# SCH_smartFemX.net
KiCad netlist of a schematic drawn in EasyEDA
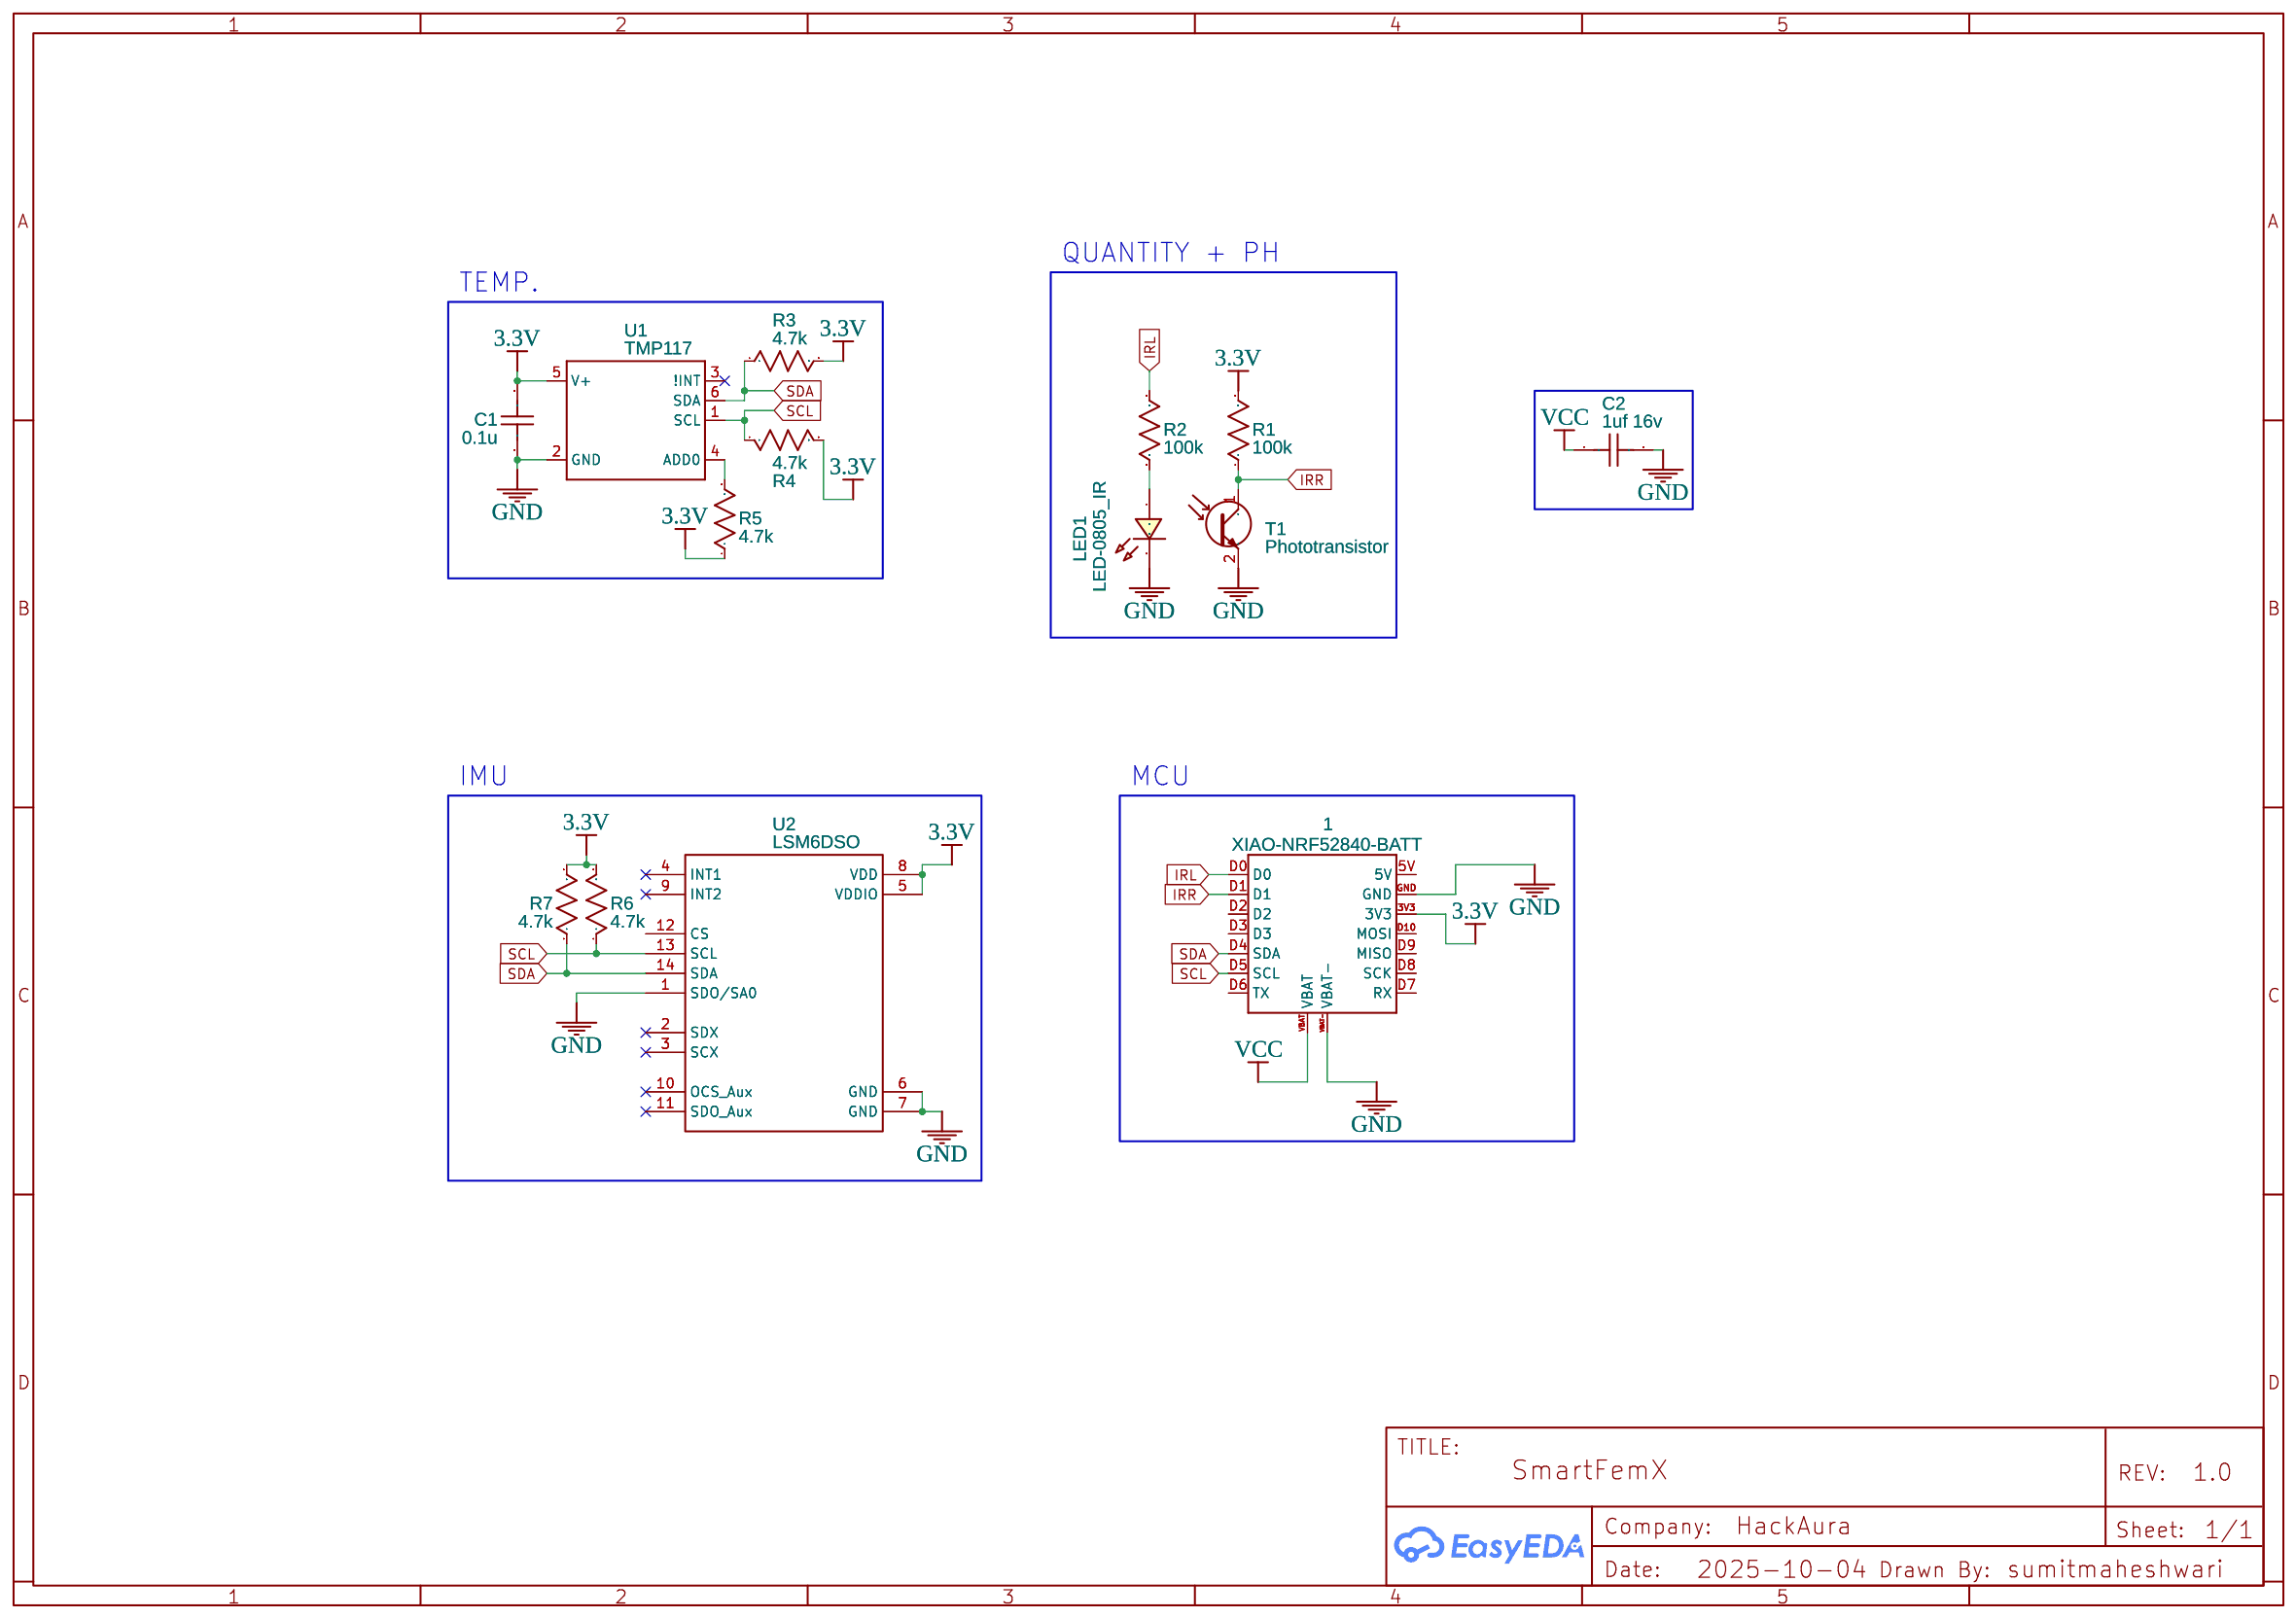
[diagram p0: schematic sheet]

(export (version "E")
  (design (tool "Eeschema 10.0.6"))
  (components
    (comp (ref "1") (value "XIAO-NRF52840-BATT") (libsource (lib "") (part "XIAO-NRF52840-BATT")))
    (comp (ref "C1") (value "0.1u") (libsource (lib "") (part "C_0805_US_1")))
    (comp (ref "C2") (value "1uf 16v") (libsource (lib "") (part "C_0805_US")))
    (comp (ref "LED1")
      (value "LED-0805_IR")
      (fields
        (field (name "Manufacturer Part") "17-21SURC/S530-A3/TR8")
        (field (name "Manufacturer") "EVERLIGHT(台湾亿光)")
      )
      (libsource (lib "") (part "LED-0805_R"))
    )
    (comp (ref "R1") (value "100k") (libsource (lib "") (part "R_0805_US")))
    (comp (ref "R2") (value "100k") (libsource (lib "") (part "R_0805_US")))
    (comp (ref "R3") (value "4.7k") (libsource (lib "") (part "R_0805_US_3")))
    (comp (ref "R4") (value "4.7k") (libsource (lib "") (part "R_0805_US_2")))
    (comp (ref "R5") (value "4.7k") (libsource (lib "") (part "R_0805_US")))
    (comp (ref "R6") (value "4.7k") (libsource (lib "") (part "R_0805_US_1")))
    (comp (ref "R7") (value "4.7k") (libsource (lib "") (part "R_0805_US")))
    (comp (ref "T1")
      (value "Phototransistor")
      (fields (field (name "Manufacturer Part") "VEMT3700-GS08") (field (name "Manufacturer") "Vishay"))
      (libsource (lib "") (part "Phototransistor_VEMT3700-GS08_SMD"))
    )
    (comp (ref "U1") (value "TMP117") (libsource (lib "") (part "TMP117")))
    (comp (ref "U2")
      (value "LSM6DSO")
      (fields (field (name "Manufacturer") "ST"))
      (libsource (lib "") (part "LSM6DSO"))
    )
  )
  (nets
    (net (code "1") (name "3.3V") (class "Default")
      (node (ref "1") (pin "3V3") (pinfunction "3V3_3V3") (pintype "passive"))
      (node (ref "C1") (pin "2") (pinfunction "2_2") (pintype "unspecified"))
      (node (ref "R1") (pin "2") (pinfunction "2_2") (pintype "unspecified"))
      (node (ref "R3") (pin "2") (pinfunction "2_2") (pintype "unspecified"))
      (node (ref "R4") (pin "2") (pinfunction "2_2") (pintype "unspecified"))
      (node (ref "R5") (pin "1") (pinfunction "1_1") (pintype "unspecified"))
      (node (ref "R6") (pin "2") (pinfunction "2_2") (pintype "unspecified"))
      (node (ref "R7") (pin "2") (pinfunction "2_2") (pintype "unspecified"))
      (node (ref "U1") (pin "5") (pinfunction "V+_5") (pintype "bidirectional"))
      (node (ref "U2") (pin "5") (pinfunction "VDDIO_5") (pintype "unspecified"))
      (node (ref "U2") (pin "8") (pinfunction "VDD_8") (pintype "unspecified"))
    )
    (net (code "2") (name "GND") (class "Default")
      (node (ref "1") (pin "GND") (pinfunction "GND_GND") (pintype "passive"))
      (node (ref "1") (pin "VBAT-") (pinfunction "VBAT-_VBAT-") (pintype "input"))
      (node (ref "C1") (pin "1") (pinfunction "1_1") (pintype "unspecified"))
      (node (ref "C2") (pin "2") (pinfunction "2_2") (pintype "unspecified"))
      (node (ref "LED1") (pin "2") (pinfunction "2_2") (pintype "unspecified"))
      (node (ref "T1") (pin "2") (pinfunction "E_2") (pintype "unspecified"))
      (node (ref "U1") (pin "2") (pinfunction "GND_2") (pintype "bidirectional"))
      (node (ref "U2") (pin "1") (pinfunction "SDO/SA0_1") (pintype "unspecified"))
      (node (ref "U2") (pin "6") (pinfunction "GND_6") (pintype "unspecified"))
      (node (ref "U2") (pin "7") (pinfunction "GND_7") (pintype "unspecified"))
    )
    (net (code "3") (name "IRL") (class "Default")
      (node (ref "1") (pin "D0") (pinfunction "D0_D0") (pintype "bidirectional"))
      (node (ref "R2") (pin "2") (pinfunction "2_2") (pintype "unspecified"))
    )
    (net (code "4") (name "IRR") (class "Default")
      (node (ref "1") (pin "D1") (pinfunction "D1_D1") (pintype "bidirectional"))
      (node (ref "R1") (pin "1") (pinfunction "1_1") (pintype "unspecified"))
      (node (ref "T1") (pin "1") (pinfunction "C_1") (pintype "unspecified"))
    )
    (net (code "5") (name "Net-(LED1-Pad1)") (class "Default")
      (node (ref "LED1") (pin "1") (pinfunction "1_1") (pintype "unspecified"))
      (node (ref "R2") (pin "1") (pinfunction "1_1") (pintype "unspecified"))
    )
    (net (code "6") (name "Net-(U1-ADD0)") (class "Default")
      (node (ref "R5") (pin "2") (pinfunction "2_2") (pintype "unspecified"))
      (node (ref "U1") (pin "4") (pinfunction "ADD0_4") (pintype "bidirectional"))
    )
    (net (code "7") (name "SCL") (class "Default")
      (node (ref "1") (pin "D5") (pinfunction "SCL_D5") (pintype "bidirectional"))
      (node (ref "R4") (pin "1") (pinfunction "1_1") (pintype "unspecified"))
      (node (ref "R6") (pin "1") (pinfunction "1_1") (pintype "unspecified"))
      (node (ref "U1") (pin "1") (pinfunction "SCL_1") (pintype "bidirectional"))
      (node (ref "U2") (pin "13") (pinfunction "SCL_13") (pintype "unspecified"))
    )
    (net (code "8") (name "SDA") (class "Default")
      (node (ref "1") (pin "D4") (pinfunction "SDA_D4") (pintype "bidirectional"))
      (node (ref "R3") (pin "1") (pinfunction "1_1") (pintype "unspecified"))
      (node (ref "R7") (pin "1") (pinfunction "1_1") (pintype "unspecified"))
      (node (ref "U1") (pin "6") (pinfunction "SDA_6") (pintype "bidirectional"))
      (node (ref "U2") (pin "14") (pinfunction "SDA_14") (pintype "unspecified"))
    )
    (net (code "9") (name "VCC") (class "Default")
      (node (ref "1") (pin "VBAT") (pinfunction "VBAT_VBAT") (pintype "input"))
      (node (ref "C2") (pin "1") (pinfunction "1_1") (pintype "unspecified"))
    )
    (net (code "10") (name "unconnected-(1-MISO-PadD9)") (class "Default")
      (node (ref "1") (pin "D9") (pinfunction "MISO_D9") (pintype "bidirectional"))
    )
    (net (code "11") (name "unconnected-(1-MOSI-PadD10)") (class "Default")
      (node (ref "1") (pin "D10") (pinfunction "MOSI_D10") (pintype "bidirectional"))
    )
    (net (code "12") (name "unconnected-(1-Pad5V)") (class "Default")
      (node (ref "1") (pin "5V") (pinfunction "5V_5V") (pintype "passive"))
    )
    (net (code "13") (name "unconnected-(1-PadD2)") (class "Default")
      (node (ref "1") (pin "D2") (pinfunction "D2_D2") (pintype "bidirectional"))
    )
    (net (code "14") (name "unconnected-(1-PadD3)") (class "Default")
      (node (ref "1") (pin "D3") (pinfunction "D3_D3") (pintype "bidirectional"))
    )
    (net (code "15") (name "unconnected-(1-RX-PadD7)") (class "Default")
      (node (ref "1") (pin "D7") (pinfunction "RX_D7") (pintype "bidirectional"))
    )
    (net (code "16") (name "unconnected-(1-SCK-PadD8)") (class "Default")
      (node (ref "1") (pin "D8") (pinfunction "SCK_D8") (pintype "bidirectional"))
    )
    (net (code "17") (name "unconnected-(1-TX-PadD6)") (class "Default")
      (node (ref "1") (pin "D6") (pinfunction "TX_D6") (pintype "bidirectional"))
    )
    (net (code "18") (name "unconnected-(U1-!INT-Pad3)") (class "Default")
      (node (ref "U1") (pin "3") (pinfunction "!INT_3") (pintype "bidirectional+no_connect"))
    )
    (net (code "19") (name "unconnected-(U2-CS-Pad12)") (class "Default")
      (node (ref "U2") (pin "12") (pinfunction "CS_12") (pintype "unspecified"))
    )
    (net (code "20") (name "unconnected-(U2-INT1-Pad4)") (class "Default")
      (node (ref "U2") (pin "4") (pinfunction "INT1_4") (pintype "unspecified+no_connect"))
    )
    (net (code "21") (name "unconnected-(U2-INT2-Pad9)") (class "Default")
      (node (ref "U2") (pin "9") (pinfunction "INT2_9") (pintype "unspecified+no_connect"))
    )
    (net (code "22") (name "unconnected-(U2-OCS_Aux-Pad10)") (class "Default")
      (node (ref "U2") (pin "10") (pinfunction "OCS_Aux_10") (pintype "unspecified+no_connect"))
    )
    (net (code "23") (name "unconnected-(U2-SCX-Pad3)") (class "Default")
      (node (ref "U2") (pin "3") (pinfunction "SCX_3") (pintype "unspecified+no_connect"))
    )
    (net (code "24") (name "unconnected-(U2-SDO_Aux-Pad11)") (class "Default")
      (node (ref "U2") (pin "11") (pinfunction "SDO_Aux_11") (pintype "unspecified+no_connect"))
    )
    (net (code "25") (name "unconnected-(U2-SDX-Pad2)") (class "Default")
      (node (ref "U2") (pin "2") (pinfunction "SDX_2") (pintype "unspecified+no_connect"))
    )
  )
)
